# probe.net
KiCad netlist of a schematic drawn in EAGLE
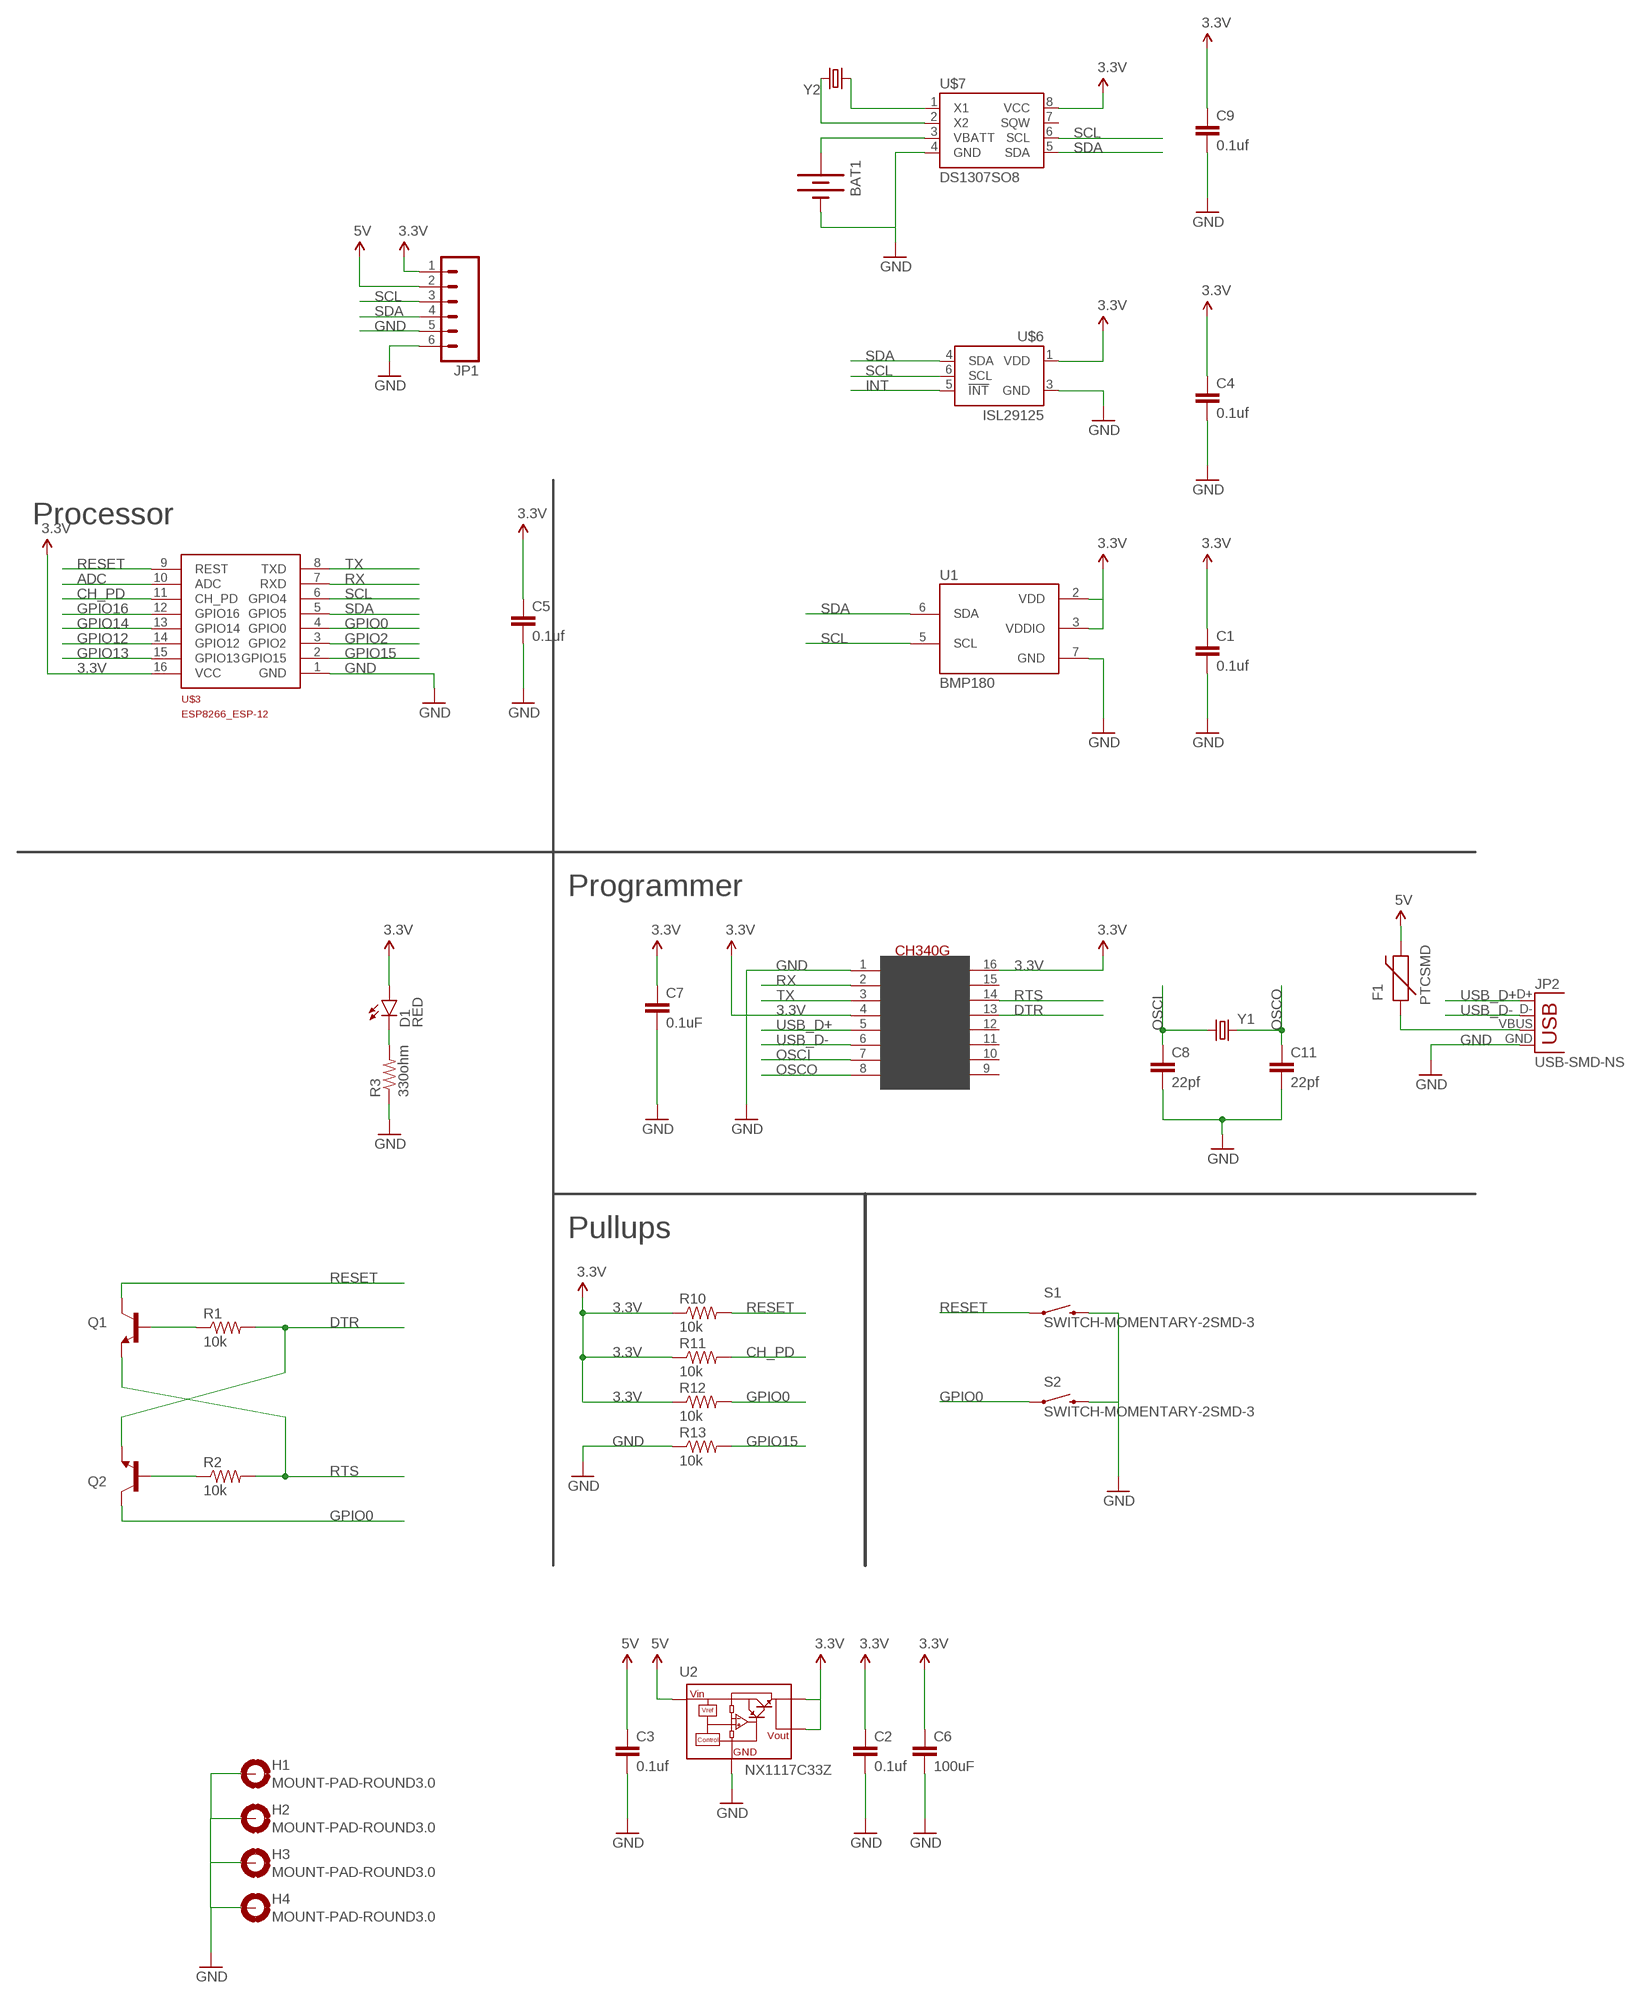
[diagram p0: schematic, sheet 1]

(export (version "E")
  (design (tool "Eeschema 10.0.6"))
  (components
    (comp (ref "BAT1")
      (value "BATTERY12MM")
      (footprint "eagle-import:BATTCON_12MM")
      (libsource (lib "eagle-import") (part "BATTERY12MM"))
    )
    (comp (ref "C1")
      (value "0.1uf")
      (footprint "eagle-import:1206")
      (libsource (lib "eagle-import") (part "CAP1206"))
    )
    (comp (ref "C2")
      (value "0.1uf")
      (footprint "eagle-import:1206")
      (libsource (lib "eagle-import") (part "CAP1206"))
    )
    (comp (ref "C3")
      (value "0.1uf")
      (footprint "eagle-import:1206")
      (libsource (lib "eagle-import") (part "CAP1206"))
    )
    (comp (ref "C4")
      (value "0.1uf")
      (footprint "eagle-import:1206")
      (libsource (lib "eagle-import") (part "CAP1206"))
    )
    (comp (ref "C5")
      (value "0.1uf")
      (footprint "eagle-import:1206")
      (libsource (lib "eagle-import") (part "CAP1206"))
    )
    (comp (ref "C6")
      (value "100uF")
      (footprint "eagle-import:1210")
      (libsource (lib "eagle-import") (part "100UF6.3V20%(1210)"))
    )
    (comp (ref "C7")
      (value "0.1uF")
      (footprint "eagle-import:1206")
      (libsource (lib "eagle-import") (part "CAP1206"))
    )
    (comp (ref "C8")
      (value "22pf")
      (footprint "eagle-import:1206")
      (libsource (lib "eagle-import") (part "CAP1206"))
    )
    (comp (ref "C9")
      (value "0.1uf")
      (footprint "eagle-import:1206")
      (libsource (lib "eagle-import") (part "CAP1206"))
    )
    (comp (ref "C11")
      (value "22pf")
      (footprint "eagle-import:1206")
      (libsource (lib "eagle-import") (part "CAP1206"))
    )
    (comp (ref "D1")
      (value "RED")
      (footprint "eagle-import:LED-1206")
      (libsource (lib "eagle-import") (part "LED-RED1206"))
    )
    (comp (ref "F1")
      (value "PTCSMD")
      (footprint "eagle-import:PTC-1206")
      (libsource (lib "eagle-import") (part "PTCSMD"))
    )
    (comp (ref "H1")
      (value "MOUNT-PAD-ROUND3.0")
      (footprint "eagle-import:3,0-PAD")
      (libsource (lib "eagle-import") (part "MOUNT-PAD-ROUND3.0"))
    )
    (comp (ref "H2")
      (value "MOUNT-PAD-ROUND3.0")
      (footprint "eagle-import:3,0-PAD")
      (libsource (lib "eagle-import") (part "MOUNT-PAD-ROUND3.0"))
    )
    (comp (ref "H3")
      (value "MOUNT-PAD-ROUND3.0")
      (footprint "eagle-import:3,0-PAD")
      (libsource (lib "eagle-import") (part "MOUNT-PAD-ROUND3.0"))
    )
    (comp (ref "H4")
      (value "MOUNT-PAD-ROUND3.0")
      (footprint "eagle-import:3,0-PAD")
      (libsource (lib "eagle-import") (part "MOUNT-PAD-ROUND3.0"))
    )
    (comp (ref "JP1")
      (value "M06SMD-1MM")
      (footprint "eagle-import:1X06-1MM")
      (libsource (lib "eagle-import") (part "M06SMD-1MM"))
    )
    (comp (ref "JP2")
      (value "USB-SMD-NS")
      (footprint "eagle-import:USB-MINIB-NOSTOP")
      (libsource (lib "eagle-import") (part "USB-SMD-NS"))
    )
    (comp (ref "Q1")
      (value "TRANSISTOR_NPNSOT23-3")
      (footprint "eagle-import:SOT23-3")
      (libsource (lib "eagle-import") (part "TRANSISTOR_NPNSOT23-3"))
    )
    (comp (ref "Q2")
      (value "TRANSISTOR_NPNSOT23-3")
      (footprint "eagle-import:SOT23-3")
      (libsource (lib "eagle-import") (part "TRANSISTOR_NPNSOT23-3"))
    )
    (comp (ref "R1")
      (value "10k")
      (footprint "eagle-import:1206")
      (libsource (lib "eagle-import") (part "RESISTOR1206"))
    )
    (comp (ref "R2")
      (value "10k")
      (footprint "eagle-import:1206")
      (libsource (lib "eagle-import") (part "RESISTOR1206"))
    )
    (comp (ref "R3")
      (value "330ohm")
      (footprint "eagle-import:1206")
      (libsource (lib "eagle-import") (part "RESISTOR1206"))
    )
    (comp (ref "R10")
      (value "10k")
      (footprint "eagle-import:1206")
      (libsource (lib "eagle-import") (part "RESISTOR1206"))
    )
    (comp (ref "R11")
      (value "10k")
      (footprint "eagle-import:1206")
      (libsource (lib "eagle-import") (part "RESISTOR1206"))
    )
    (comp (ref "R12")
      (value "10k")
      (footprint "eagle-import:1206")
      (libsource (lib "eagle-import") (part "RESISTOR1206"))
    )
    (comp (ref "R13")
      (value "10k")
      (footprint "eagle-import:1206")
      (libsource (lib "eagle-import") (part "RESISTOR1206"))
    )
    (comp (ref "S1")
      (value "SWITCH-MOMENTARY-2SMD-3")
      (footprint "eagle-import:TACTILE_SWITCH_SMD-3")
      (libsource (lib "eagle-import") (part "SWITCH-MOMENTARY-2SMD-3"))
    )
    (comp (ref "S2")
      (value "SWITCH-MOMENTARY-2SMD-3")
      (footprint "eagle-import:TACTILE_SWITCH_SMD-3")
      (libsource (lib "eagle-import") (part "SWITCH-MOMENTARY-2SMD-3"))
    )
    (comp (ref "U$2")
      (value "CH340G")
      (footprint "eagle-import:SOIC16")
      (libsource (lib "eagle-import") (part "CH340G"))
    )
    (comp (ref "U$3")
      (value "ESP8266_ESP-12")
      (footprint "eagle-import:ESP8266-ESP12")
      (libsource (lib "eagle-import") (part "ESP8266_ESP-12"))
    )
    (comp (ref "U$6")
      (value "ISL29125")
      (footprint "eagle-import:ODFN-LD-6")
      (libsource (lib "eagle-import") (part "ISL29125"))
    )
    (comp (ref "U$7")
      (value "DS1307SO8")
      (footprint "eagle-import:SO08")
      (libsource (lib "eagle-import") (part "DS1307SO8"))
    )
    (comp (ref "U1")
      (value "BMP180")
      (footprint "eagle-import:BMP180")
      (libsource (lib "eagle-import") (part "BMP180"))
    )
    (comp (ref "U2")
      (value "NX1117C33Z")
      (footprint "eagle-import:SOT223")
      (fields (field (name "TOLERANCE") "1.25%") (field (name "VOLTAGE") "5.0V"))
      (libsource (lib "eagle-import") (part "NX1117CZ33"))
    )
    (comp (ref "Y1")
      (value "CRYSTALSMD")
      (footprint "eagle-import:HC49UP")
      (libsource (lib "eagle-import") (part "CRYSTALSMD"))
    )
    (comp (ref "Y2")
      (value "CRYSTALTC38H")
      (footprint "eagle-import:TC38H")
      (libsource (lib "eagle-import") (part "CRYSTALTC38H"))
    )
  )
  (nets
    (net (code "1") (name "/ADC") (class "Default")
      (node (ref "U$3") (pin "10") (pinfunction "ADC_10") (pintype "bidirectional"))
    )
    (net (code "2") (name "/CH_PD") (class "Default")
      (node (ref "R11") (pin "2") (pinfunction "2_2") (pintype "passive"))
      (node (ref "U$3") (pin "11") (pinfunction "CH_PD_11") (pintype "bidirectional"))
    )
    (net (code "3") (name "/DTR") (class "Default")
      (node (ref "Q2") (pin "2") (pinfunction "E_2") (pintype "passive"))
      (node (ref "R1") (pin "2") (pinfunction "2_2") (pintype "passive"))
      (node (ref "U$2") (pin "13") (pinfunction "DTR_13") (pintype "bidirectional"))
    )
    (net (code "4") (name "/GPIO0") (class "Default")
      (node (ref "Q2") (pin "3") (pinfunction "C_3") (pintype "passive"))
      (node (ref "R12") (pin "2") (pinfunction "2_2") (pintype "passive"))
      (node (ref "S2") (pin "1") (pinfunction "1_1") (pintype "passive"))
      (node (ref "U$3") (pin "4") (pinfunction "GPIO0_4") (pintype "bidirectional"))
    )
    (net (code "5") (name "/GPIO2") (class "Default")
      (node (ref "U$3") (pin "3") (pinfunction "GPIO2_3") (pintype "bidirectional"))
    )
    (net (code "6") (name "/GPIO12") (class "Default")
      (node (ref "U$3") (pin "14") (pinfunction "GPIO12_14") (pintype "bidirectional"))
    )
    (net (code "7") (name "/GPIO13") (class "Default")
      (node (ref "U$3") (pin "15") (pinfunction "GPIO13_15") (pintype "bidirectional"))
    )
    (net (code "8") (name "/GPIO14") (class "Default")
      (node (ref "U$3") (pin "13") (pinfunction "GPIO14_13") (pintype "bidirectional"))
    )
    (net (code "9") (name "/GPIO15") (class "Default")
      (node (ref "R13") (pin "2") (pinfunction "2_2") (pintype "passive"))
      (node (ref "U$3") (pin "2") (pinfunction "GPIO15_2") (pintype "bidirectional"))
    )
    (net (code "10") (name "/GPIO16") (class "Default")
      (node (ref "U$3") (pin "12") (pinfunction "GPIO16_12") (pintype "bidirectional"))
    )
    (net (code "11") (name "/INT") (class "Default")
      (node (ref "U$6") (pin "5") (pinfunction "~{INT}_5") (pintype "bidirectional"))
    )
    (net (code "12") (name "/OSCI") (class "Default")
      (node (ref "C8") (pin "1") (pinfunction "1_1") (pintype "passive"))
      (node (ref "U$2") (pin "7") (pinfunction "XI_7") (pintype "bidirectional"))
      (node (ref "Y1") (pin "1") (pinfunction "1_1") (pintype "passive"))
    )
    (net (code "13") (name "/OSCO") (class "Default")
      (node (ref "C11") (pin "1") (pinfunction "1_1") (pintype "passive"))
      (node (ref "U$2") (pin "8") (pinfunction "XO_8") (pintype "bidirectional"))
      (node (ref "Y1") (pin "2") (pinfunction "2_2") (pintype "passive"))
    )
    (net (code "14") (name "/RESET") (class "Default")
      (node (ref "Q1") (pin "3") (pinfunction "C_3") (pintype "passive"))
      (node (ref "R10") (pin "2") (pinfunction "2_2") (pintype "passive"))
      (node (ref "S1") (pin "1") (pinfunction "1_1") (pintype "passive"))
      (node (ref "U$3") (pin "9") (pinfunction "REST_9") (pintype "bidirectional"))
    )
    (net (code "15") (name "/RTS") (class "Default")
      (node (ref "Q1") (pin "2") (pinfunction "E_2") (pintype "passive"))
      (node (ref "R2") (pin "2") (pinfunction "2_2") (pintype "passive"))
      (node (ref "U$2") (pin "14") (pinfunction "RTS_14") (pintype "bidirectional"))
    )
    (net (code "16") (name "/RX") (class "Default")
      (node (ref "U$2") (pin "2") (pinfunction "TX_2") (pintype "bidirectional"))
      (node (ref "U$3") (pin "7") (pinfunction "RXD_7") (pintype "bidirectional"))
    )
    (net (code "17") (name "/SCL") (class "Default")
      (node (ref "JP1") (pin "3") (pinfunction "3_3") (pintype "passive"))
      (node (ref "U$3") (pin "6") (pinfunction "GPIO4_6") (pintype "bidirectional"))
      (node (ref "U$6") (pin "6") (pinfunction "SCL_6") (pintype "bidirectional"))
      (node (ref "U$7") (pin "6") (pinfunction "SCL_6") (pintype "bidirectional"))
      (node (ref "U1") (pin "5") (pinfunction "SCL_5") (pintype "input"))
    )
    (net (code "18") (name "/SDA") (class "Default")
      (node (ref "JP1") (pin "4") (pinfunction "4_4") (pintype "passive"))
      (node (ref "U$3") (pin "5") (pinfunction "GPIO5_5") (pintype "bidirectional"))
      (node (ref "U$6") (pin "4") (pinfunction "SDA_4") (pintype "bidirectional"))
      (node (ref "U$7") (pin "5") (pinfunction "SDA_5") (pintype "bidirectional"))
      (node (ref "U1") (pin "6") (pinfunction "SDA_6") (pintype "bidirectional"))
    )
    (net (code "19") (name "/TX") (class "Default")
      (node (ref "U$2") (pin "3") (pinfunction "RX_3") (pintype "bidirectional"))
      (node (ref "U$3") (pin "8") (pinfunction "TXD_8") (pintype "bidirectional"))
    )
    (net (code "20") (name "/USB_D+") (class "Default")
      (node (ref "JP2") (pin "D+") (pinfunction "D+_D+") (pintype "bidirectional"))
      (node (ref "U$2") (pin "5") (pinfunction "D+_5") (pintype "bidirectional"))
    )
    (net (code "21") (name "/USB_D-") (class "Default")
      (node (ref "JP2") (pin "D-") (pinfunction "D-_D-") (pintype "bidirectional"))
      (node (ref "U$2") (pin "6") (pinfunction "D-_6") (pintype "bidirectional"))
    )
    (net (code "22") (name "3.3V") (class "Default")
      (node (ref "C1") (pin "1") (pinfunction "1_1") (pintype "passive"))
      (node (ref "C2") (pin "1") (pinfunction "1_1") (pintype "passive"))
      (node (ref "C4") (pin "1") (pinfunction "1_1") (pintype "passive"))
      (node (ref "C5") (pin "1") (pinfunction "1_1") (pintype "passive"))
      (node (ref "C6") (pin "1") (pinfunction "1_1") (pintype "passive"))
      (node (ref "C7") (pin "1") (pinfunction "1_1") (pintype "passive"))
      (node (ref "C9") (pin "1") (pinfunction "1_1") (pintype "passive"))
      (node (ref "D1") (pin "A") (pinfunction "A_A") (pintype "passive"))
      (node (ref "JP1") (pin "1") (pinfunction "1_1") (pintype "passive"))
      (node (ref "R10") (pin "1") (pinfunction "1_1") (pintype "passive"))
      (node (ref "R11") (pin "1") (pinfunction "1_1") (pintype "passive"))
      (node (ref "R12") (pin "1") (pinfunction "1_1") (pintype "passive"))
      (node (ref "U$2") (pin "16") (pinfunction "VCC_16") (pintype "bidirectional"))
      (node (ref "U$2") (pin "4") (pinfunction "V3_4") (pintype "bidirectional"))
      (node (ref "U$3") (pin "16") (pinfunction "VCC_16") (pintype "bidirectional"))
      (node (ref "U$6") (pin "1") (pinfunction "VDD_1") (pintype "bidirectional"))
      (node (ref "U$7") (pin "8") (pinfunction "VCC_8") (pintype "bidirectional"))
      (node (ref "U1") (pin "2") (pinfunction "VDD_2") (pintype "power_in"))
      (node (ref "U1") (pin "3") (pinfunction "VDDIO_3") (pintype "power_in"))
      (node (ref "U2") (pin "2") (pinfunction "VOUT1_2") (pintype "output"))
      (node (ref "U2") (pin "4") (pinfunction "VOUT_4") (pintype "output"))
    )
    (net (code "23") (name "5V") (class "Default")
      (node (ref "C3") (pin "1") (pinfunction "1_1") (pintype "passive"))
      (node (ref "F1") (pin "2") (pinfunction "2_2") (pintype "bidirectional"))
      (node (ref "JP1") (pin "2") (pinfunction "2_2") (pintype "passive"))
      (node (ref "U2") (pin "3") (pinfunction "VIN_3") (pintype "input"))
    )
    (net (code "24") (name "GND") (class "Default")
      (node (ref "BAT1") (pin "GND") (pinfunction "-_GND") (pintype "power_in"))
      (node (ref "C1") (pin "2") (pinfunction "2_2") (pintype "passive"))
      (node (ref "C11") (pin "2") (pinfunction "2_2") (pintype "passive"))
      (node (ref "C2") (pin "2") (pinfunction "2_2") (pintype "passive"))
      (node (ref "C3") (pin "2") (pinfunction "2_2") (pintype "passive"))
      (node (ref "C4") (pin "2") (pinfunction "2_2") (pintype "passive"))
      (node (ref "C5") (pin "2") (pinfunction "2_2") (pintype "passive"))
      (node (ref "C6") (pin "2") (pinfunction "2_2") (pintype "passive"))
      (node (ref "C7") (pin "2") (pinfunction "2_2") (pintype "passive"))
      (node (ref "C8") (pin "2") (pinfunction "2_2") (pintype "passive"))
      (node (ref "C9") (pin "2") (pinfunction "2_2") (pintype "passive"))
      (node (ref "H1") (pin "B3,0") (pinfunction "MOUNT_B3,0") (pintype "passive"))
      (node (ref "H2") (pin "B3,0") (pinfunction "MOUNT_B3,0") (pintype "passive"))
      (node (ref "H3") (pin "B3,0") (pinfunction "MOUNT_B3,0") (pintype "passive"))
      (node (ref "H4") (pin "B3,0") (pinfunction "MOUNT_B3,0") (pintype "passive"))
      (node (ref "JP1") (pin "5") (pinfunction "5_5") (pintype "passive"))
      (node (ref "JP1") (pin "6") (pinfunction "6_6") (pintype "passive"))
      (node (ref "JP2") (pin "GND") (pinfunction "GND_GND") (pintype "bidirectional"))
      (node (ref "R13") (pin "1") (pinfunction "1_1") (pintype "passive"))
      (node (ref "R3") (pin "1") (pinfunction "1_1") (pintype "passive"))
      (node (ref "S1") (pin "4") (pinfunction "2_4") (pintype "passive"))
      (node (ref "S2") (pin "4") (pinfunction "2_4") (pintype "passive"))
      (node (ref "U$2") (pin "1") (pinfunction "GND_1") (pintype "bidirectional"))
      (node (ref "U$3") (pin "1") (pinfunction "GND_1") (pintype "bidirectional"))
      (node (ref "U$6") (pin "3") (pinfunction "GND_3") (pintype "bidirectional"))
      (node (ref "U$7") (pin "4") (pinfunction "GND_4") (pintype "bidirectional"))
      (node (ref "U1") (pin "7") (pinfunction "GND_7") (pintype "power_in"))
      (node (ref "U2") (pin "1") (pinfunction "GND_1") (pintype "passive"))
    )
    (net (code "25") (name "Net-(BAT1-+)") (class "Default")
      (node (ref "BAT1") (pin "PWR@1") (pinfunction "+_PWR@1") (pintype "power_in"))
      (node (ref "U$7") (pin "3") (pinfunction "VBATT_3") (pintype "bidirectional"))
    )
    (net (code "26") (name "Net-(D1-PadC)") (class "Default")
      (node (ref "D1") (pin "C") (pinfunction "C_C") (pintype "passive"))
      (node (ref "R3") (pin "2") (pinfunction "2_2") (pintype "passive"))
    )
    (net (code "27") (name "Net-(F1-Pad1)") (class "Default")
      (node (ref "F1") (pin "1") (pinfunction "1_1") (pintype "bidirectional"))
      (node (ref "JP2") (pin "VBUS") (pinfunction "VBUS_VBUS") (pintype "bidirectional"))
    )
    (net (code "28") (name "Net-(Q1-B)") (class "Default")
      (node (ref "Q1") (pin "1") (pinfunction "B_1") (pintype "passive"))
      (node (ref "R1") (pin "1") (pinfunction "1_1") (pintype "passive"))
    )
    (net (code "29") (name "Net-(Q2-B)") (class "Default")
      (node (ref "Q2") (pin "1") (pinfunction "B_1") (pintype "passive"))
      (node (ref "R2") (pin "1") (pinfunction "1_1") (pintype "passive"))
    )
    (net (code "30") (name "Net-(U$7-X1)") (class "Default")
      (node (ref "U$7") (pin "1") (pinfunction "X1_1") (pintype "bidirectional"))
      (node (ref "Y2") (pin "1") (pinfunction "1_1") (pintype "passive"))
    )
    (net (code "31") (name "Net-(U$7-X2)") (class "Default")
      (node (ref "U$7") (pin "2") (pinfunction "X2_2") (pintype "bidirectional"))
      (node (ref "Y2") (pin "2") (pinfunction "2_2") (pintype "passive"))
    )
    (net (code "32") (name "unconnected-(U$2-CTS-Pad9)") (class "Default")
      (node (ref "U$2") (pin "9") (pinfunction "CTS_9") (pintype "bidirectional"))
    )
    (net (code "33") (name "unconnected-(U$2-DCD-Pad12)") (class "Default")
      (node (ref "U$2") (pin "12") (pinfunction "DCD_12") (pintype "bidirectional"))
    )
    (net (code "34") (name "unconnected-(U$2-DSR-Pad10)") (class "Default")
      (node (ref "U$2") (pin "10") (pinfunction "DSR_10") (pintype "bidirectional"))
    )
    (net (code "35") (name "unconnected-(U$2-RI-Pad11)") (class "Default")
      (node (ref "U$2") (pin "11") (pinfunction "RI_11") (pintype "bidirectional"))
    )
    (net (code "36") (name "unconnected-(U$2-RS232-Pad15)") (class "Default")
      (node (ref "U$2") (pin "15") (pinfunction "RS232_15") (pintype "bidirectional"))
    )
    (net (code "37") (name "unconnected-(U$7-SQW-Pad7)") (class "Default")
      (node (ref "U$7") (pin "7") (pinfunction "SQW_7") (pintype "bidirectional"))
    )
  )
)
